# 11-Stimulation.net
KiCad netlist of a schematic drawn in Altium Designer
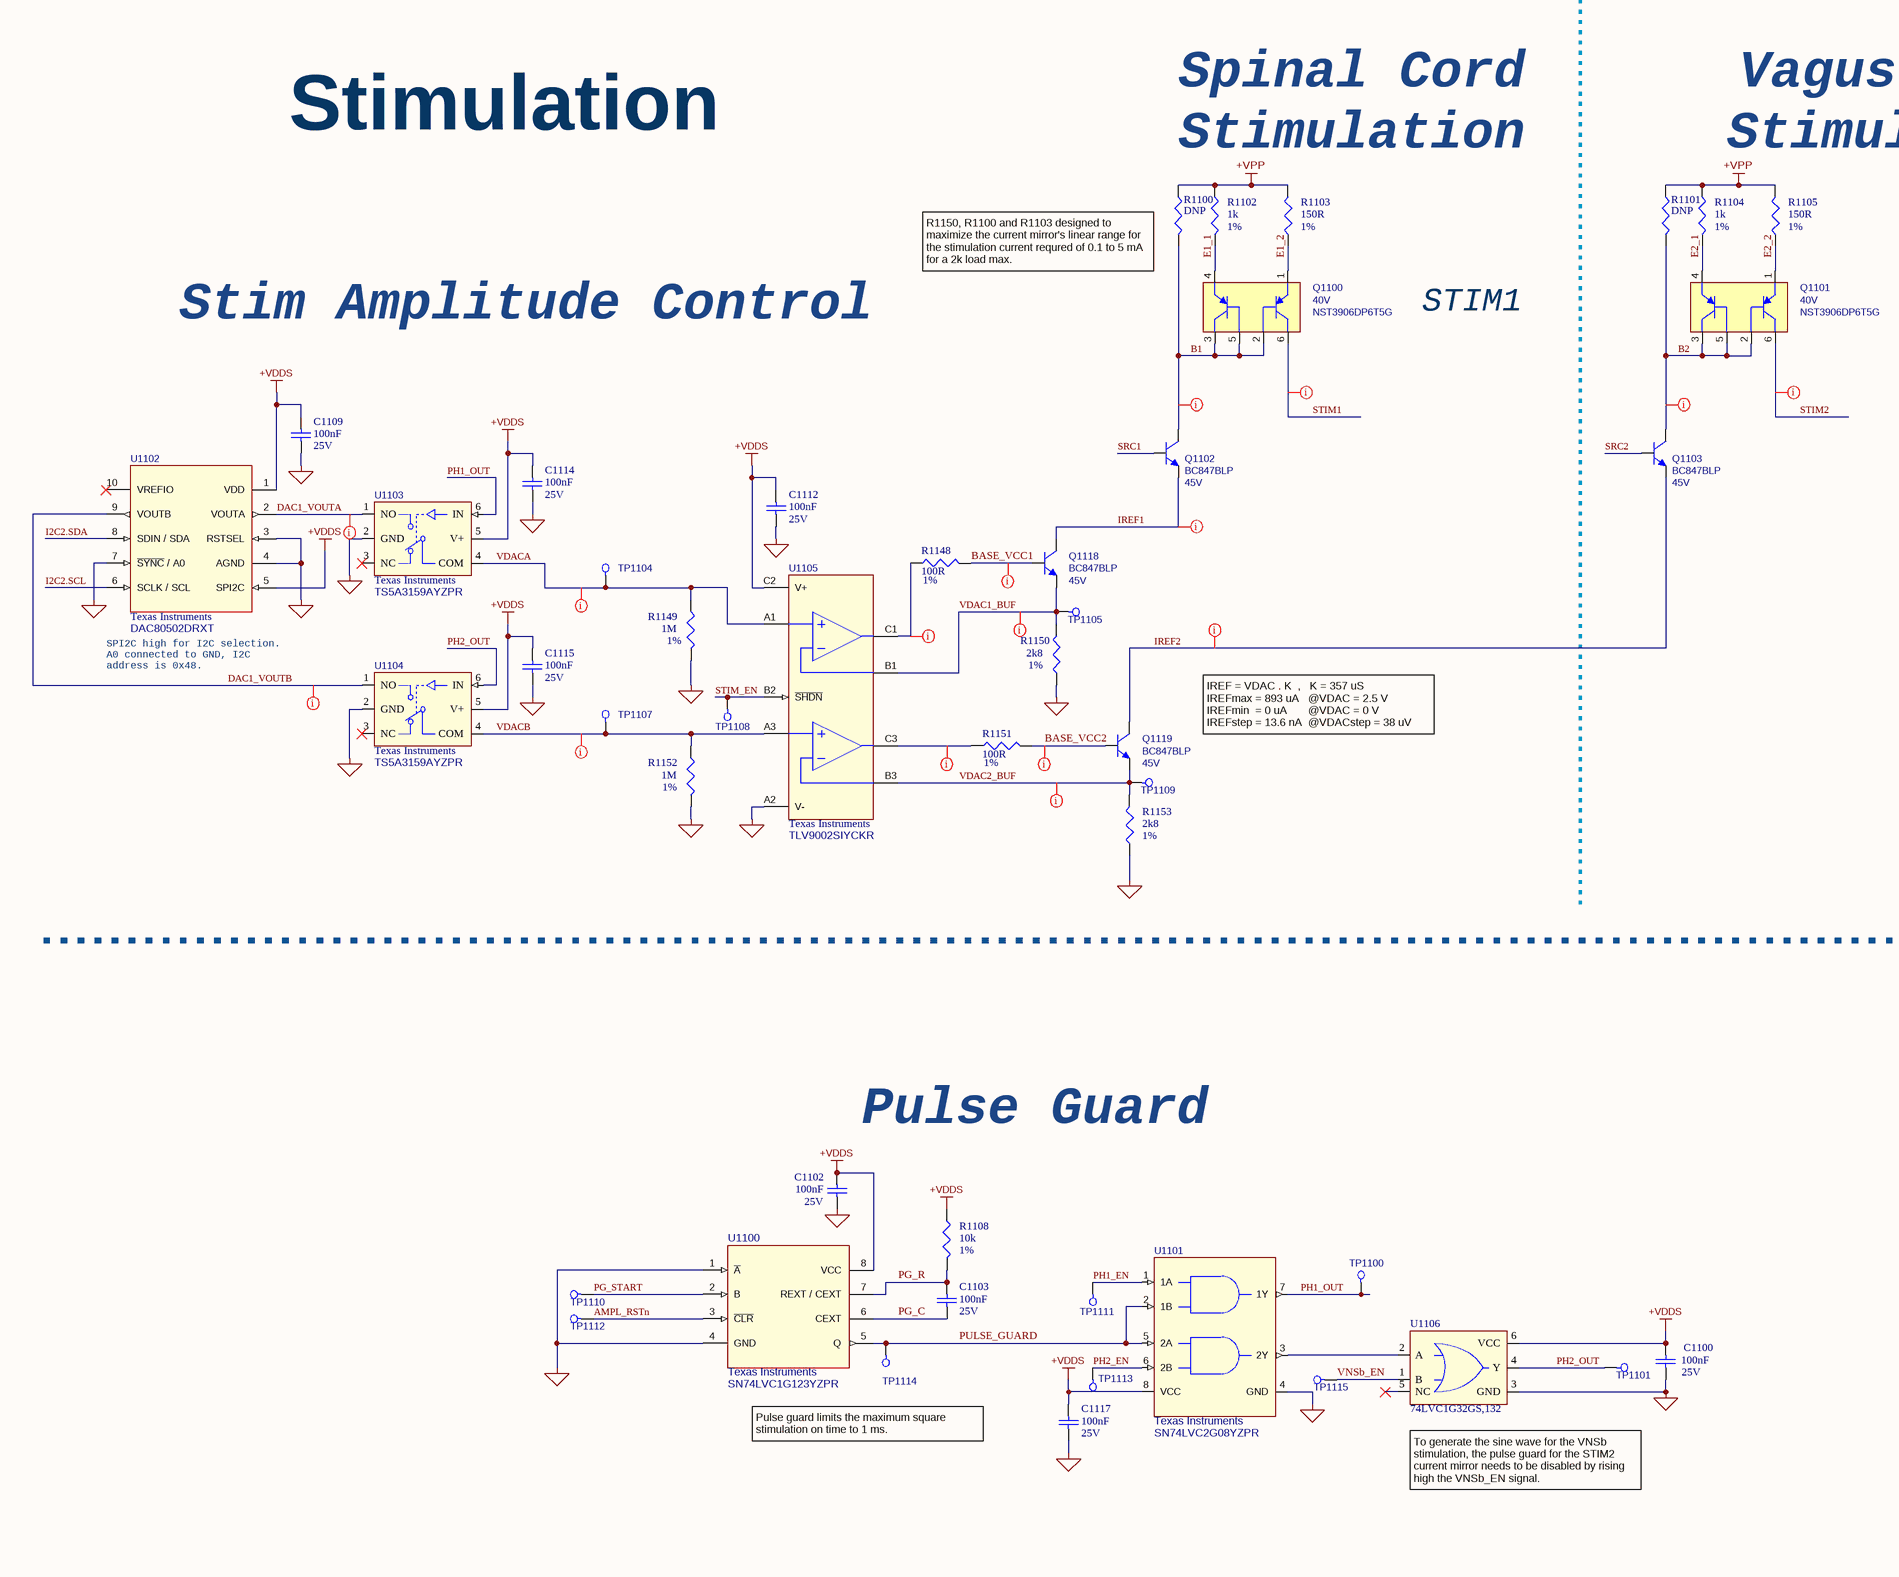
[diagram p0: 11-Stimulation.SchDoc, left]
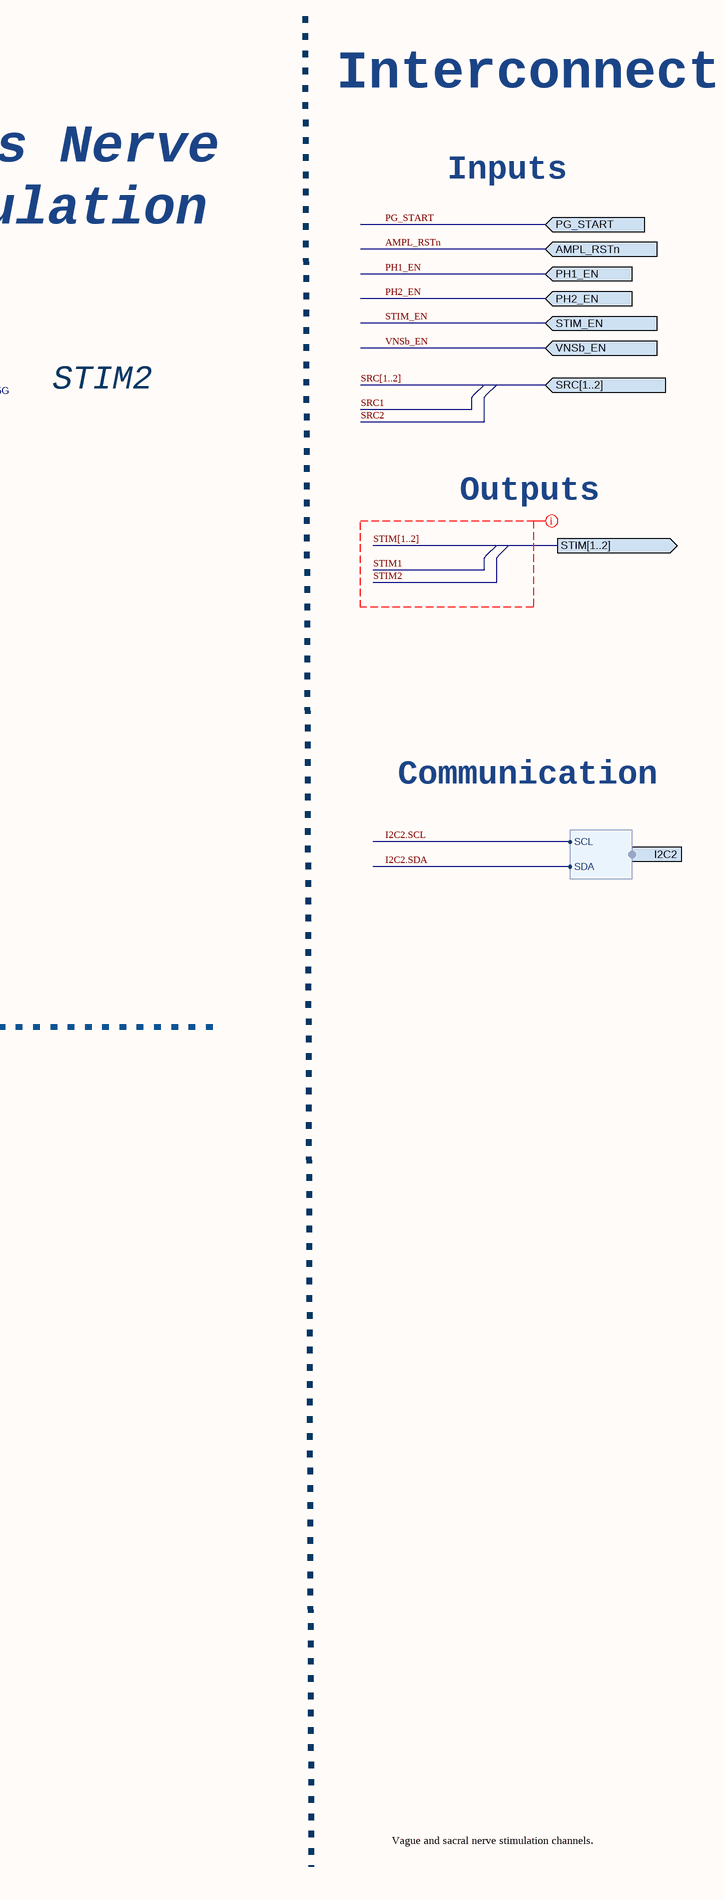
[diagram p1: 11-Stimulation.SchDoc, right]

(export (version "E")
  (design (tool "Eeschema 10.0.6"))
  (components
    (comp (ref "C1100")
      (value "100nF")
      (footprint "C0201_C")
      (fields
        (field (name "MANUFACTURER") "Murata")
        (field (name "MANUFACTURER PART NUMBER") "GRM033R61E104KE14J")
        (field (name "RATED DC VOLTAGE (URDC)") "25V")
      )
      (libsource (lib "MP-LIBRARY") (part "GRM033R61E104KE14J"))
    )
    (comp (ref "C1102")
      (value "100nF")
      (footprint "C0201_C")
      (fields
        (field (name "MANUFACTURER") "Murata")
        (field (name "MANUFACTURER PART NUMBER") "GRM033R61E104KE14J")
        (field (name "RATED DC VOLTAGE (URDC)") "25V")
      )
      (libsource (lib "MP-LIBRARY") (part "GRM033R61E104KE14J"))
    )
    (comp (ref "C1103")
      (value "100nF")
      (footprint "C0201_C")
      (fields
        (field (name "MANUFACTURER") "Murata")
        (field (name "MANUFACTURER PART NUMBER") "GRM033R61E104KE14J")
        (field (name "RATED DC VOLTAGE (URDC)") "25V")
      )
      (libsource (lib "MP-LIBRARY") (part "GRM033R61E104KE14J"))
    )
    (comp (ref "C1109")
      (value "100nF")
      (footprint "C0201_C")
      (fields
        (field (name "MANUFACTURER") "Murata")
        (field (name "MANUFACTURER PART NUMBER") "GRM033R61E104KE14J")
        (field (name "RATED DC VOLTAGE (URDC)") "25V")
      )
      (libsource (lib "MP-LIBRARY") (part "GRM033R61E104KE14J"))
    )
    (comp (ref "C1112")
      (value "100nF")
      (footprint "C0201_C")
      (fields
        (field (name "MANUFACTURER") "Murata")
        (field (name "MANUFACTURER PART NUMBER") "GRM033R61E104KE14J")
        (field (name "RATED DC VOLTAGE (URDC)") "25V")
      )
      (libsource (lib "MP-LIBRARY") (part "GRM033R61E104KE14J"))
    )
    (comp (ref "C1114")
      (value "100nF")
      (footprint "C0201_C")
      (fields
        (field (name "MANUFACTURER") "Murata")
        (field (name "MANUFACTURER PART NUMBER") "GRM033R61E104KE14J")
        (field (name "RATED DC VOLTAGE (URDC)") "25V")
      )
      (libsource (lib "MP-LIBRARY") (part "GRM033R61E104KE14J"))
    )
    (comp (ref "C1115")
      (value "100nF")
      (footprint "C0201_C")
      (fields
        (field (name "MANUFACTURER") "Murata")
        (field (name "MANUFACTURER PART NUMBER") "GRM033R61E104KE14J")
        (field (name "RATED DC VOLTAGE (URDC)") "25V")
      )
      (libsource (lib "MP-LIBRARY") (part "GRM033R61E104KE14J"))
    )
    (comp (ref "C1117")
      (value "100nF")
      (footprint "C0201_C")
      (fields
        (field (name "MANUFACTURER") "Murata")
        (field (name "MANUFACTURER PART NUMBER") "GRM033R61E104KE14J")
        (field (name "RATED DC VOLTAGE (URDC)") "25V")
      )
      (libsource (lib "MP-LIBRARY") (part "GRM033R61E104KE14J"))
    )
    (comp (ref "Q1100")
      (value "NST3906DP6T5G")
      (footprint "DIODESINC_SOT-963-6")
      (description "TRANS 2PNP 40V 0.2A SOT963")
      (fields (field (name "MANUFACTURER") "ON Semi") (field (name "RATING") "40V"))
      (libsource (lib "MP-LIBRARY") (part "NST3906DP6T5G"))
    )
    (comp (ref "Q1101")
      (value "NST3906DP6T5G")
      (footprint "DIODESINC_SOT-963-6")
      (description "TRANS 2PNP 40V 0.2A SOT963")
      (fields (field (name "MANUFACTURER") "ON Semi") (field (name "RATING") "40V"))
      (libsource (lib "MP-LIBRARY") (part "NST3906DP6T5G"))
    )
    (comp (ref "Q1102")
      (value "BC847BLP")
      (footprint "DIODESINC_X1-DFN1006-3")
      (description "Transistor, NPN, 45V, 100mA, DFN1006")
      (fields
        (field (name "MANUFACTURER") "Diodes Inc")
        (field (name "RATING") "45V")
        (field (name "MANUFACTURER PART NUMBER") "BC847BLP-7B")
      )
      (libsource (lib "MP-LIBRARY") (part "BC847BLP-7B"))
    )
    (comp (ref "Q1103")
      (value "BC847BLP")
      (footprint "DIODESINC_X1-DFN1006-3")
      (description "Transistor, NPN, 45V, 100mA, DFN1006")
      (fields
        (field (name "MANUFACTURER") "Diodes Inc")
        (field (name "RATING") "45V")
        (field (name "MANUFACTURER PART NUMBER") "BC847BLP-7B")
      )
      (libsource (lib "MP-LIBRARY") (part "BC847BLP-7B"))
    )
    (comp (ref "Q1118")
      (value "BC847BLP")
      (footprint "DIODESINC_X1-DFN1006-3")
      (description "Transistor, NPN, 45V, 100mA, DFN1006")
      (fields
        (field (name "MANUFACTURER") "Diodes Inc")
        (field (name "RATING") "45V")
        (field (name "MANUFACTURER PART NUMBER") "BC847BLP-7B")
      )
      (libsource (lib "MP-LIBRARY") (part "BC847BLP-7B"))
    )
    (comp (ref "Q1119")
      (value "BC847BLP")
      (footprint "DIODESINC_X1-DFN1006-3")
      (description "Transistor, NPN, 45V, 100mA, DFN1006")
      (fields
        (field (name "MANUFACTURER") "Diodes Inc")
        (field (name "RATING") "45V")
        (field (name "MANUFACTURER PART NUMBER") "BC847BLP-7B")
      )
      (libsource (lib "MP-LIBRARY") (part "BC847BLP-7B"))
    )
    (comp (ref "R1100")
      (value "DNP")
      (footprint "R0201_C")
      (fields (field (name "Comment") "RES_DNP_0201"))
      (libsource (lib "MP-LIBRARY") (part "RES_DNP_0201"))
    )
    (comp (ref "R1101")
      (value "DNP")
      (footprint "R0201_C")
      (fields (field (name "Comment") "RES_DNP_0201"))
      (libsource (lib "MP-LIBRARY") (part "RES_DNP_0201"))
    )
    (comp (ref "R1102")
      (value "1k")
      (footprint "R0201_C")
      (fields
        (field (name "MANUFACTURER") "Vishay")
        (field (name "MANUFACTURER PART NUMBER") "CRCW02011K00FNED")
        (field (name "TOLERANCE") "1%")
        (field (name "POWER") "50mW")
      )
      (libsource (lib "MP-LIBRARY") (part "CRCW02011K00FNED"))
    )
    (comp (ref "R1103")
      (value "150R")
      (footprint "R0201_C")
      (fields
        (field (name "MANUFACTURER") "Vishay")
        (field (name "MANUFACTURER PART NUMBER") "CRCW0201150RFNED")
        (field (name "TOLERANCE") "1%")
        (field (name "POWER") "50mW")
      )
      (libsource (lib "MP-LIBRARY") (part "CRCW0201150RFNED"))
    )
    (comp (ref "R1104")
      (value "1k")
      (footprint "R0201_C")
      (fields
        (field (name "MANUFACTURER") "Vishay")
        (field (name "MANUFACTURER PART NUMBER") "CRCW02011K00FNED")
        (field (name "TOLERANCE") "1%")
        (field (name "POWER") "50mW")
      )
      (libsource (lib "MP-LIBRARY") (part "CRCW02011K00FNED"))
    )
    (comp (ref "R1105")
      (value "150R")
      (footprint "R0201_C")
      (fields
        (field (name "MANUFACTURER") "Vishay")
        (field (name "MANUFACTURER PART NUMBER") "CRCW0201150RFNED")
        (field (name "TOLERANCE") "1%")
        (field (name "POWER") "50mW")
      )
      (libsource (lib "MP-LIBRARY") (part "CRCW0201150RFNED"))
    )
    (comp (ref "R1108")
      (value "10k")
      (footprint "R0201_C")
      (fields
        (field (name "MANUFACTURER") "Vishay")
        (field (name "MANUFACTURER PART NUMBER") "CRCW020110K0FNED")
        (field (name "TOLERANCE") "1%")
        (field (name "POWER") "50mW")
      )
      (libsource (lib "MP-LIBRARY") (part "CRCW020110K0FNED"))
    )
    (comp (ref "R1148")
      (value "100R")
      (footprint "R0201_C")
      (fields
        (field (name "MANUFACTURER") "Vishay")
        (field (name "MANUFACTURER PART NUMBER") "CRCW0201100RFNED")
        (field (name "TOLERANCE") "1%")
        (field (name "POWER") "50mW")
      )
      (libsource (lib "MP-LIBRARY") (part "CRCW0201100RFNED"))
    )
    (comp (ref "R1149")
      (value "1M")
      (footprint "R0201_C")
      (fields
        (field (name "MANUFACTURER") "Vishay")
        (field (name "MANUFACTURER PART NUMBER") "CRCW02011M00FNED")
        (field (name "TOLERANCE") "1%")
        (field (name "POWER") "50mW")
      )
      (libsource (lib "MP-LIBRARY") (part "CRCW02011M00FNED"))
    )
    (comp (ref "R1150")
      (value "2k8")
      (footprint "R0201_C")
      (fields
        (field (name "MANUFACTURER") "Vishay")
        (field (name "MANUFACTURER PART NUMBER") "CRCW02012K80FNED")
        (field (name "TOLERANCE") "1%")
        (field (name "POWER") "50mW")
      )
      (libsource (lib "MP-LIBRARY") (part "CRCW02012K80FNED"))
    )
    (comp (ref "R1151")
      (value "100R")
      (footprint "R0201_C")
      (fields
        (field (name "MANUFACTURER") "Vishay")
        (field (name "MANUFACTURER PART NUMBER") "CRCW0201100RFNED")
        (field (name "TOLERANCE") "1%")
        (field (name "POWER") "50mW")
      )
      (libsource (lib "MP-LIBRARY") (part "CRCW0201100RFNED"))
    )
    (comp (ref "R1152")
      (value "1M")
      (footprint "R0201_C")
      (fields
        (field (name "MANUFACTURER") "Vishay")
        (field (name "MANUFACTURER PART NUMBER") "CRCW02011M00FNED")
        (field (name "TOLERANCE") "1%")
        (field (name "POWER") "50mW")
      )
      (libsource (lib "MP-LIBRARY") (part "CRCW02011M00FNED"))
    )
    (comp (ref "R1153")
      (value "2k8")
      (footprint "R0201_C")
      (fields
        (field (name "MANUFACTURER") "Vishay")
        (field (name "MANUFACTURER PART NUMBER") "CRCW02012K80FNED")
        (field (name "TOLERANCE") "1%")
        (field (name "POWER") "50mW")
      )
      (libsource (lib "MP-LIBRARY") (part "CRCW02012K80FNED"))
    )
    (comp (ref "TP1100")
      (value "Test Point")
      (footprint "testpad_0.9mm")
      (description "Test pad, 0.90mm circular pad")
      (libsource (lib "MP-LIBRARY") (part "Test Point"))
    )
    (comp (ref "TP1101")
      (value "Test Point")
      (footprint "testpad_0.9mm")
      (description "Test pad, 0.90mm circular pad")
      (libsource (lib "MP-LIBRARY") (part "Test Point"))
    )
    (comp (ref "TP1104")
      (value "Test Point")
      (footprint "testpad_0.9mm")
      (description "Test pad, 0.90mm circular pad")
      (libsource (lib "MP-LIBRARY") (part "Test Point"))
    )
    (comp (ref "TP1105")
      (value "Test Point")
      (footprint "testpad_0.9mm")
      (description "Test pad, 0.90mm circular pad")
      (libsource (lib "MP-LIBRARY") (part "Test Point"))
    )
    (comp (ref "TP1107")
      (value "Test Point")
      (footprint "testpad_0.9mm")
      (description "Test pad, 0.90mm circular pad")
      (libsource (lib "MP-LIBRARY") (part "Test Point"))
    )
    (comp (ref "TP1108")
      (value "Test Point")
      (footprint "testpad_0.9mm")
      (description "Test pad, 0.90mm circular pad")
      (libsource (lib "MP-LIBRARY") (part "Test Point"))
    )
    (comp (ref "TP1109")
      (value "Test Point")
      (footprint "testpad_0.9mm")
      (description "Test pad, 0.90mm circular pad")
      (libsource (lib "MP-LIBRARY") (part "Test Point"))
    )
    (comp (ref "TP1110")
      (value "Test Point")
      (footprint "testpad_0.9mm")
      (description "Test pad, 0.90mm circular pad")
      (libsource (lib "MP-LIBRARY") (part "Test Point"))
    )
    (comp (ref "TP1111")
      (value "Test Point")
      (footprint "testpad_0.9mm")
      (description "Test pad, 0.90mm circular pad")
      (libsource (lib "MP-LIBRARY") (part "Test Point"))
    )
    (comp (ref "TP1112")
      (value "Test Point")
      (footprint "testpad_0.9mm")
      (description "Test pad, 0.90mm circular pad")
      (libsource (lib "MP-LIBRARY") (part "Test Point"))
    )
    (comp (ref "TP1113")
      (value "Test Point")
      (footprint "testpad_0.9mm")
      (description "Test pad, 0.90mm circular pad")
      (libsource (lib "MP-LIBRARY") (part "Test Point"))
    )
    (comp (ref "TP1114")
      (value "Test Point")
      (footprint "testpad_0.9mm")
      (description "Test pad, 0.90mm circular pad")
      (libsource (lib "MP-LIBRARY") (part "Test Point"))
    )
    (comp (ref "TP1115")
      (value "Test Point")
      (footprint "testpad_0.9mm")
      (description "Test pad, 0.90mm circular pad")
      (libsource (lib "MP-LIBRARY") (part "Test Point"))
    )
    (comp (ref "U1100")
      (value "SN74LVC1G123YZPR")
      (footprint "TI_YZP0008")
      (description "Monostable, RC set, dual triggers, BGA-8")
      (fields (field (name "MANUFACTURER") "Texas Instruments"))
      (libsource (lib "MP-LIBRARY") (part "SN74LVC1G123YZPR"))
    )
    (comp (ref "U1101")
      (value "SN74LVC2G08YZPR")
      (footprint "TI_YZP0008")
      (description "AND gate, Dual 2-input, BGA-8")
      (fields (field (name "MANUFACTURER") "Texas Instruments"))
      (libsource (lib "MP-LIBRARY") (part "SN74LVC2G08YZPR"))
    )
    (comp (ref "U1102")
      (value "DAC80502DRXT")
      (footprint "TI_DRX0010A")
      (description "DAC, 16-bit, Dual channel, SPI/I2C, WSON-10")
      (fields (field (name "MANUFACTURER") "Texas Instruments"))
      (libsource (lib "MP-LIBRARY") (part "DAC80502DRXT"))
    )
    (comp (ref "U1103")
      (value "TS5A3159AYZPR")
      (footprint "TI_YZP6")
      (description "Analog Switch, SPDT, 2:1, DSBGA6")
      (fields (field (name "MANUFACTURER") "Texas Instruments"))
      (libsource (lib "MP-LIBRARY") (part "TS5A3159AYZPR"))
    )
    (comp (ref "U1104")
      (value "TS5A3159AYZPR")
      (footprint "TI_YZP6")
      (description "Analog Switch, SPDT, 2:1, DSBGA6")
      (fields (field (name "MANUFACTURER") "Texas Instruments"))
      (libsource (lib "MP-LIBRARY") (part "TS5A3159AYZPR"))
    )
    (comp (ref "U1105")
      (value "TLV9002SIYCKR")
      (footprint "TI_YCK0009")
      (description "Op Amp, Dual, Rail-to-Rail, 1MHz, BGA-9")
      (fields (field (name "MANUFACTURER") "Texas Instruments"))
      (libsource (lib "MP-LIBRARY") (part "TLV9002SIYCKR"))
    )
    (comp (ref "U1106")
      (value "74LVC1G32GS,132")
      (footprint "74LVC1G3157GS132")
      (description "OR Gate IC 1 Channel 6-XSON, SOT1202 (1x1)")
      (fields (field (name "MANUFACTURER") "Nexperia"))
      (libsource (lib "MP-LIBRARY") (part "74LVC1G32GS,132"))
    )
  )
  (nets
    (net (code "2") (name "+VDDS") (class "Default")
      (node (ref "C1100") (pin "2") (pinfunction "2_2") (pintype "passive"))
      (node (ref "C1102") (pin "2") (pinfunction "2_2") (pintype "passive"))
      (node (ref "C1109") (pin "2") (pinfunction "2_2") (pintype "passive"))
      (node (ref "C1112") (pin "2") (pinfunction "2_2") (pintype "passive"))
      (node (ref "C1114") (pin "2") (pinfunction "2_2") (pintype "passive"))
      (node (ref "C1115") (pin "2") (pinfunction "2_2") (pintype "passive"))
      (node (ref "C1117") (pin "2") (pinfunction "2_2") (pintype "passive"))
      (node (ref "R1108") (pin "1") (pinfunction "1_1") (pintype "passive"))
      (node (ref "U1100") (pin "8") (pinfunction "VCC_8") (pintype "power_in"))
      (node (ref "U1101") (pin "8") (pinfunction "VCC_8") (pintype "power_in"))
      (node (ref "U1102") (pin "1") (pinfunction "VDD_1") (pintype "power_in"))
      (node (ref "U1102") (pin "5") (pinfunction "SPI2C_5") (pintype "input"))
      (node (ref "U1103") (pin "5") (pinfunction "V+_5") (pintype "power_in"))
      (node (ref "U1104") (pin "5") (pinfunction "V+_5") (pintype "power_in"))
      (node (ref "U1105") (pin "C2") (pinfunction "V+_C2") (pintype "power_in"))
      (node (ref "U1106") (pin "6") (pinfunction "VCC_6") (pintype "passive"))
    )
    (net (code "3") (name "+VPP") (class "Default")
      (node (ref "R1100") (pin "1") (pinfunction "1_1") (pintype "passive"))
      (node (ref "R1101") (pin "1") (pinfunction "1_1") (pintype "passive"))
      (node (ref "R1102") (pin "1") (pinfunction "1_1") (pintype "passive"))
      (node (ref "R1103") (pin "2") (pinfunction "2_2") (pintype "passive"))
      (node (ref "R1104") (pin "1") (pinfunction "1_1") (pintype "passive"))
      (node (ref "R1105") (pin "2") (pinfunction "2_2") (pintype "passive"))
    )
    (net (code "4") (name "/AMPL_RSTn") (class "Default")
      (node (ref "TP1112") (pin "1") (pinfunction "1_1") (pintype "passive"))
      (node (ref "U1100") (pin "3") (pinfunction "~{CLR}_3") (pintype "input"))
    )
    (net (code "5") (name "/B1") (class "Default")
      (node (ref "Q1100") (pin "2") (pinfunction "B2_2") (pintype "passive"))
      (node (ref "Q1100") (pin "3") (pinfunction "C1_3") (pintype "passive"))
      (node (ref "Q1100") (pin "5") (pinfunction "B1_5") (pintype "passive"))
      (node (ref "Q1102") (pin "3") (pinfunction "C_3") (pintype "passive"))
      (node (ref "R1100") (pin "2") (pinfunction "2_2") (pintype "passive"))
    )
    (net (code "6") (name "/B2") (class "Default")
      (node (ref "Q1101") (pin "2") (pinfunction "B2_2") (pintype "passive"))
      (node (ref "Q1101") (pin "3") (pinfunction "C1_3") (pintype "passive"))
      (node (ref "Q1101") (pin "5") (pinfunction "B1_5") (pintype "passive"))
      (node (ref "Q1103") (pin "3") (pinfunction "C_3") (pintype "passive"))
      (node (ref "R1101") (pin "2") (pinfunction "2_2") (pintype "passive"))
    )
    (net (code "7") (name "/BASE_VCC1") (class "Default")
      (node (ref "Q1118") (pin "1") (pinfunction "B_1") (pintype "passive"))
      (node (ref "R1148") (pin "2") (pinfunction "2_2") (pintype "passive"))
    )
    (net (code "8") (name "/BASE_VCC2") (class "Default")
      (node (ref "Q1119") (pin "1") (pinfunction "B_1") (pintype "passive"))
      (node (ref "R1151") (pin "2") (pinfunction "2_2") (pintype "passive"))
    )
    (net (code "9") (name "/DAC1_VOUTA") (class "Default")
      (node (ref "U1102") (pin "2") (pinfunction "VOUTA_2") (pintype "output"))
      (node (ref "U1103") (pin "1") (pinfunction "NO_1") (pintype "passive"))
    )
    (net (code "10") (name "/DAC1_VOUTB") (class "Default")
      (node (ref "U1102") (pin "9") (pinfunction "VOUTB_9") (pintype "output"))
      (node (ref "U1104") (pin "1") (pinfunction "NO_1") (pintype "passive"))
    )
    (net (code "11") (name "/E1_1") (class "Default")
      (node (ref "Q1100") (pin "4") (pinfunction "E1_4") (pintype "passive"))
      (node (ref "R1102") (pin "2") (pinfunction "2_2") (pintype "passive"))
    )
    (net (code "12") (name "/E1_2") (class "Default")
      (node (ref "Q1100") (pin "1") (pinfunction "E2_1") (pintype "passive"))
      (node (ref "R1103") (pin "1") (pinfunction "1_1") (pintype "passive"))
    )
    (net (code "13") (name "/E2_1") (class "Default")
      (node (ref "Q1101") (pin "4") (pinfunction "E1_4") (pintype "passive"))
      (node (ref "R1104") (pin "2") (pinfunction "2_2") (pintype "passive"))
    )
    (net (code "14") (name "/E2_2") (class "Default")
      (node (ref "Q1101") (pin "1") (pinfunction "E2_1") (pintype "passive"))
      (node (ref "R1105") (pin "1") (pinfunction "1_1") (pintype "passive"))
    )
    (net (code "15") (name "/I2C2.SCL") (class "Default")
      (node (ref "U1102") (pin "6") (pinfunction "SCLK_/_SCL_6") (pintype "input"))
    )
    (net (code "16") (name "/I2C2.SDA") (class "Default")
      (node (ref "U1102") (pin "8") (pinfunction "SDIN_/_SDA_8") (pintype "input"))
    )
    (net (code "17") (name "/IREF1") (class "Default")
      (node (ref "Q1102") (pin "2") (pinfunction "E_2") (pintype "passive"))
      (node (ref "Q1118") (pin "3") (pinfunction "C_3") (pintype "passive"))
    )
    (net (code "18") (name "/IREF2") (class "Default")
      (node (ref "Q1103") (pin "2") (pinfunction "E_2") (pintype "passive"))
      (node (ref "Q1119") (pin "3") (pinfunction "C_3") (pintype "passive"))
    )
    (net (code "19") (name "/PG_C") (class "Default")
      (node (ref "C1103") (pin "1") (pinfunction "1_1") (pintype "passive"))
      (node (ref "U1100") (pin "6") (pinfunction "CEXT_6") (pintype "passive"))
    )
    (net (code "20") (name "/PG_R") (class "Default")
      (node (ref "C1103") (pin "2") (pinfunction "2_2") (pintype "passive"))
      (node (ref "R1108") (pin "2") (pinfunction "2_2") (pintype "passive"))
      (node (ref "U1100") (pin "7") (pinfunction "REXT_/_CEXT_7") (pintype "passive"))
    )
    (net (code "21") (name "/PG_START") (class "Default")
      (node (ref "TP1110") (pin "1") (pinfunction "1_1") (pintype "passive"))
      (node (ref "U1100") (pin "2") (pinfunction "B_2") (pintype "input"))
    )
    (net (code "22") (name "/PH1_EN") (class "Default")
      (node (ref "TP1111") (pin "1") (pinfunction "1_1") (pintype "passive"))
      (node (ref "U1101") (pin "1") (pinfunction "1A_1") (pintype "input"))
    )
    (net (code "23") (name "/PH1_OUT") (class "Default")
      (node (ref "TP1100") (pin "1") (pinfunction "1_1") (pintype "passive"))
      (node (ref "U1101") (pin "7") (pinfunction "1Y_7") (pintype "output"))
      (node (ref "U1103") (pin "6") (pinfunction "IN_6") (pintype "input"))
    )
    (net (code "24") (name "/PH2_EN") (class "Default")
      (node (ref "TP1113") (pin "1") (pinfunction "1_1") (pintype "passive"))
      (node (ref "U1101") (pin "6") (pinfunction "2B_6") (pintype "input"))
    )
    (net (code "25") (name "/PH2_OUT") (class "Default")
      (node (ref "TP1101") (pin "1") (pinfunction "1_1") (pintype "passive"))
      (node (ref "U1104") (pin "6") (pinfunction "IN_6") (pintype "input"))
      (node (ref "U1106") (pin "4") (pinfunction "Y_4") (pintype "passive"))
    )
    (net (code "26") (name "/PULSE_GUARD") (class "Default")
      (node (ref "TP1114") (pin "1") (pinfunction "1_1") (pintype "passive"))
      (node (ref "U1100") (pin "5") (pinfunction "Q_5") (pintype "output"))
      (node (ref "U1101") (pin "2") (pinfunction "1B_2") (pintype "input"))
      (node (ref "U1101") (pin "5") (pinfunction "2A_5") (pintype "input"))
    )
    (net (code "27") (name "/SRC1") (class "Default")
      (node (ref "Q1102") (pin "1") (pinfunction "B_1") (pintype "passive"))
    )
    (net (code "28") (name "/SRC2") (class "Default")
      (node (ref "Q1103") (pin "1") (pinfunction "B_1") (pintype "passive"))
    )
    (net (code "30") (name "/STIM1") (class "Default")
      (node (ref "Q1100") (pin "6") (pinfunction "C2_6") (pintype "passive"))
    )
    (net (code "31") (name "/STIM2") (class "Default")
      (node (ref "Q1101") (pin "6") (pinfunction "C2_6") (pintype "passive"))
    )
    (net (code "33") (name "/STIM_EN") (class "Default")
      (node (ref "TP1108") (pin "1") (pinfunction "1_1") (pintype "passive"))
      (node (ref "U1105") (pin "B2") (pinfunction "~{SHDN}_B2") (pintype "input"))
    )
    (net (code "34") (name "/VDAC1_BUF") (class "Default")
      (node (ref "Q1118") (pin "2") (pinfunction "E_2") (pintype "passive"))
      (node (ref "R1150") (pin "2") (pinfunction "2_2") (pintype "passive"))
      (node (ref "TP1105") (pin "1") (pinfunction "1_1") (pintype "passive"))
      (node (ref "U1105") (pin "B1") (pinfunction "IN1-_B1") (pintype "passive"))
    )
    (net (code "35") (name "/VDAC2_BUF") (class "Default")
      (node (ref "Q1119") (pin "2") (pinfunction "E_2") (pintype "passive"))
      (node (ref "R1153") (pin "2") (pinfunction "2_2") (pintype "passive"))
      (node (ref "TP1109") (pin "1") (pinfunction "1_1") (pintype "passive"))
      (node (ref "U1105") (pin "B3") (pinfunction "IN2-_B3") (pintype "passive"))
    )
    (net (code "36") (name "/VDACA") (class "Default")
      (node (ref "R1149") (pin "1") (pinfunction "1_1") (pintype "passive"))
      (node (ref "TP1104") (pin "1") (pinfunction "1_1") (pintype "passive"))
      (node (ref "U1103") (pin "4") (pinfunction "COM_4") (pintype "passive"))
      (node (ref "U1105") (pin "A1") (pinfunction "IN1+_A1") (pintype "passive"))
    )
    (net (code "37") (name "/VDACB") (class "Default")
      (node (ref "R1152") (pin "1") (pinfunction "1_1") (pintype "passive"))
      (node (ref "TP1107") (pin "1") (pinfunction "1_1") (pintype "passive"))
      (node (ref "U1104") (pin "4") (pinfunction "COM_4") (pintype "passive"))
      (node (ref "U1105") (pin "A3") (pinfunction "IN2+_A3") (pintype "passive"))
    )
    (net (code "38") (name "/VNSb_EN") (class "Default")
      (node (ref "TP1115") (pin "1") (pinfunction "1_1") (pintype "passive"))
      (node (ref "U1106") (pin "1") (pinfunction "B_1") (pintype "passive"))
    )
    (net (code "40") (name "GND") (class "Default")
      (node (ref "C1100") (pin "1") (pinfunction "1_1") (pintype "passive"))
      (node (ref "C1102") (pin "1") (pinfunction "1_1") (pintype "passive"))
      (node (ref "C1109") (pin "1") (pinfunction "1_1") (pintype "passive"))
      (node (ref "C1112") (pin "1") (pinfunction "1_1") (pintype "passive"))
      (node (ref "C1114") (pin "1") (pinfunction "1_1") (pintype "passive"))
      (node (ref "C1115") (pin "1") (pinfunction "1_1") (pintype "passive"))
      (node (ref "C1117") (pin "1") (pinfunction "1_1") (pintype "passive"))
      (node (ref "R1149") (pin "2") (pinfunction "2_2") (pintype "passive"))
      (node (ref "R1150") (pin "1") (pinfunction "1_1") (pintype "passive"))
      (node (ref "R1152") (pin "2") (pinfunction "2_2") (pintype "passive"))
      (node (ref "R1153") (pin "1") (pinfunction "1_1") (pintype "passive"))
      (node (ref "U1100") (pin "1") (pinfunction "~{A}_1") (pintype "input"))
      (node (ref "U1100") (pin "4") (pinfunction "GND_4") (pintype "power_in"))
      (node (ref "U1101") (pin "4") (pinfunction "GND_4") (pintype "power_in"))
      (node (ref "U1102") (pin "3") (pinfunction "RSTSEL_3") (pintype "input"))
      (node (ref "U1102") (pin "4") (pinfunction "AGND_4") (pintype "power_in"))
      (node (ref "U1102") (pin "7") (pinfunction "~{SYNC}_/_A0_7") (pintype "input"))
      (node (ref "U1103") (pin "2") (pinfunction "GND_2") (pintype "power_in"))
      (node (ref "U1104") (pin "2") (pinfunction "GND_2") (pintype "power_in"))
      (node (ref "U1105") (pin "A2") (pinfunction "V-_A2") (pintype "power_in"))
      (node (ref "U1106") (pin "3") (pinfunction "GND_3") (pintype "passive"))
    )
    (net (code "41") (name "Net-(U1101-2Y)") (class "Default")
      (node (ref "U1101") (pin "3") (pinfunction "2Y_3") (pintype "output"))
      (node (ref "U1106") (pin "2") (pinfunction "A_2") (pintype "passive"))
    )
    (net (code "42") (name "Net-(U1105-OUT1)") (class "Default")
      (node (ref "R1148") (pin "1") (pinfunction "1_1") (pintype "passive"))
      (node (ref "U1105") (pin "C1") (pinfunction "OUT1_C1") (pintype "passive"))
    )
    (net (code "43") (name "Net-(U1105-OUT2)") (class "Default")
      (node (ref "R1151") (pin "1") (pinfunction "1_1") (pintype "passive"))
      (node (ref "U1105") (pin "C3") (pinfunction "OUT2_C3") (pintype "passive"))
    )
    (net (code "44") (name "unconnected-(U1102-VREFIO-Pad10)") (class "Default")
      (node (ref "U1102") (pin "10") (pinfunction "VREFIO_10") (pintype "power_in+no_connect"))
    )
    (net (code "45") (name "unconnected-(U1103-NC-Pad3)") (class "Default")
      (node (ref "U1103") (pin "3") (pinfunction "NC_3") (pintype "passive+no_connect"))
    )
    (net (code "46") (name "unconnected-(U1104-NC-Pad3)") (class "Default")
      (node (ref "U1104") (pin "3") (pinfunction "NC_3") (pintype "passive+no_connect"))
    )
    (net (code "47") (name "unconnected-(U1106-NC-Pad5)") (class "Default")
      (node (ref "U1106") (pin "5") (pinfunction "NC_5") (pintype "passive+no_connect"))
    )
  )
)
